# v7-flex2811_4x.net
KiCad netlist of a schematic drawn in EAGLE
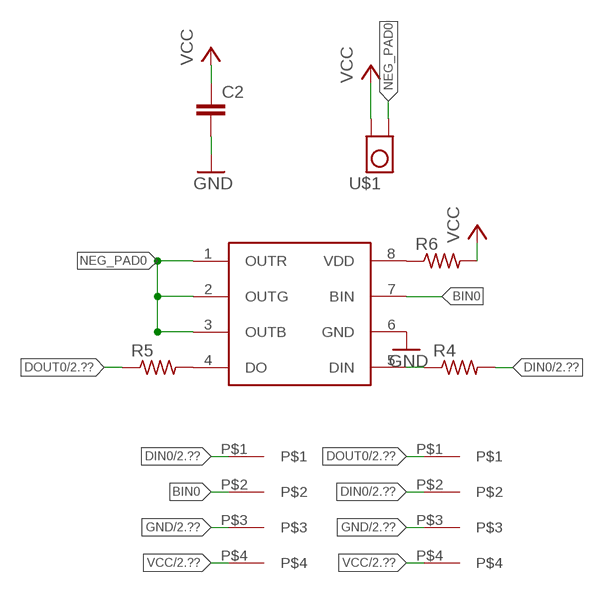
[diagram p0: schematic, sheet 1]
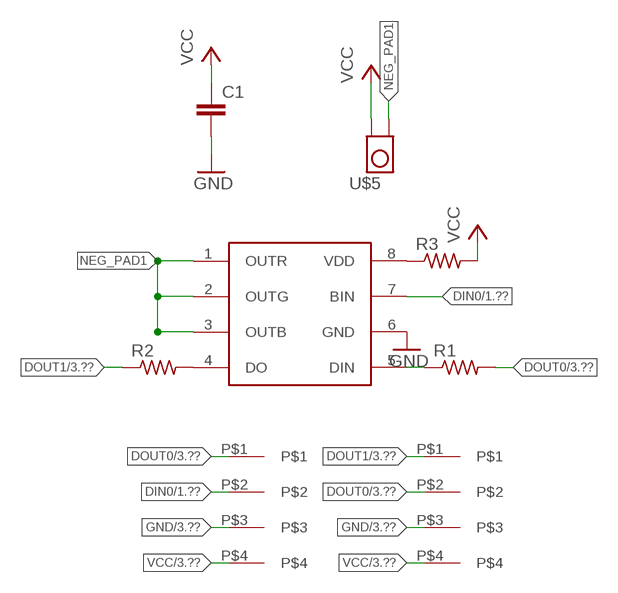
[diagram p1: schematic, sheet 2]
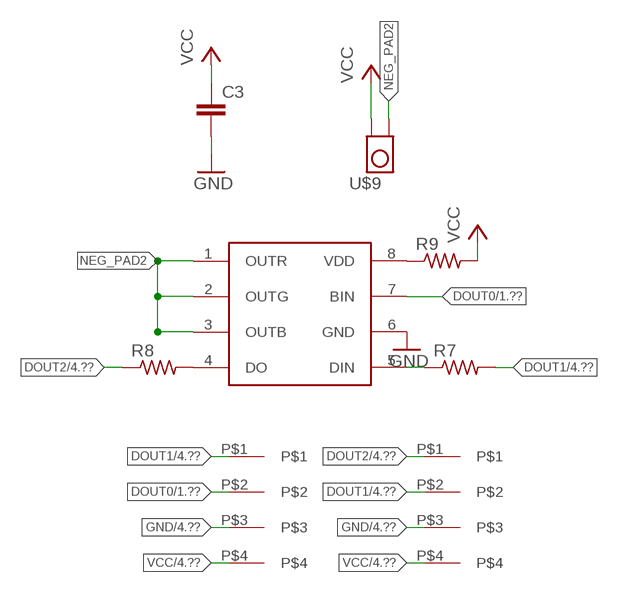
[diagram p2: schematic, sheet 3]
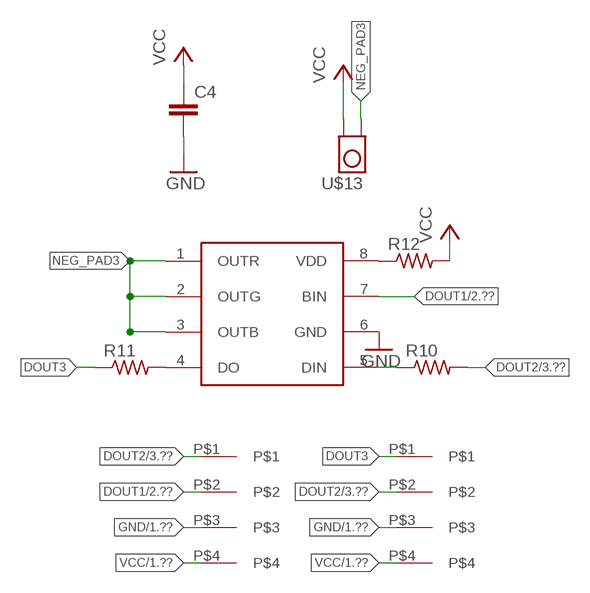
[diagram p3: schematic, sheet 4]

(export (version "E")
  (design (tool "Eeschema 10.0.6"))
  (components
    (comp (ref "C1")
      (value "C-EUC0201")
      (footprint "eagle-import:C0201")
      (libsource (lib "eagle-import") (part "C-EUC0201"))
    )
    (comp (ref "R1")
      (value "R-US_R0201")
      (footprint "eagle-import:R0201")
      (libsource (lib "eagle-import") (part "R-US_R0201"))
    )
    (comp (ref "R2")
      (value "R-US_R0201")
      (footprint "eagle-import:R0201")
      (libsource (lib "eagle-import") (part "R-US_R0201"))
    )
    (comp (ref "R3")
      (value "R-US_R0201")
      (footprint "eagle-import:R0201")
      (libsource (lib "eagle-import") (part "R-US_R0201"))
    )
    (comp (ref "U$5")
      (value "TP_4MM_MED_PAD")
      (footprint "eagle-import:TP_4MM_MED_PAD")
      (libsource (lib "eagle-import") (part "TP_4MM_MED_PAD"))
    )
    (comp (ref "U$6")
      (value "WS2818")
      (footprint "eagle-import:SO08")
      (libsource (lib "eagle-import") (part "WS2818"))
    )
    (comp (ref "U$7")
      (value "4PAD")
      (footprint "eagle-import:4PAD")
      (libsource (lib "eagle-import") (part "4PAD"))
    )
    (comp (ref "U$8")
      (value "4PAD")
      (footprint "eagle-import:4PAD")
      (libsource (lib "eagle-import") (part "4PAD"))
    )
    (comp (ref "C2")
      (value "C-EUC0201")
      (footprint "eagle-import:C0201")
      (libsource (lib "eagle-import") (part "C-EUC0201"))
    )
    (comp (ref "R4")
      (value "R-US_R0201")
      (footprint "eagle-import:R0201")
      (libsource (lib "eagle-import") (part "R-US_R0201"))
    )
    (comp (ref "R5")
      (value "R-US_R0201")
      (footprint "eagle-import:R0201")
      (libsource (lib "eagle-import") (part "R-US_R0201"))
    )
    (comp (ref "R6")
      (value "R-US_R0201")
      (footprint "eagle-import:R0201")
      (libsource (lib "eagle-import") (part "R-US_R0201"))
    )
    (comp (ref "U$1")
      (value "TP_4MM_MED_PAD")
      (footprint "eagle-import:TP_4MM_MED_PAD")
      (libsource (lib "eagle-import") (part "TP_4MM_MED_PAD"))
    )
    (comp (ref "U$2")
      (value "WS2818")
      (footprint "eagle-import:SO08")
      (libsource (lib "eagle-import") (part "WS2818"))
    )
    (comp (ref "U$3")
      (value "4PAD")
      (footprint "eagle-import:4PAD")
      (libsource (lib "eagle-import") (part "4PAD"))
    )
    (comp (ref "U$4")
      (value "4PAD")
      (footprint "eagle-import:4PAD")
      (libsource (lib "eagle-import") (part "4PAD"))
    )
    (comp (ref "C4")
      (value "C-EUC0201")
      (footprint "eagle-import:C0201")
      (libsource (lib "eagle-import") (part "C-EUC0201"))
    )
    (comp (ref "R10")
      (value "R-US_R0201")
      (footprint "eagle-import:R0201")
      (libsource (lib "eagle-import") (part "R-US_R0201"))
    )
    (comp (ref "R11")
      (value "R-US_R0201")
      (footprint "eagle-import:R0201")
      (libsource (lib "eagle-import") (part "R-US_R0201"))
    )
    (comp (ref "R12")
      (value "R-US_R0201")
      (footprint "eagle-import:R0201")
      (libsource (lib "eagle-import") (part "R-US_R0201"))
    )
    (comp (ref "U$13")
      (value "TP_4MM_MED_PAD")
      (footprint "eagle-import:TP_4MM_MED_PAD")
      (libsource (lib "eagle-import") (part "TP_4MM_MED_PAD"))
    )
    (comp (ref "U$14")
      (value "WS2818")
      (footprint "eagle-import:SO08")
      (libsource (lib "eagle-import") (part "WS2818"))
    )
    (comp (ref "U$15")
      (value "4PAD")
      (footprint "eagle-import:4PAD")
      (libsource (lib "eagle-import") (part "4PAD"))
    )
    (comp (ref "U$16")
      (value "4PAD")
      (footprint "eagle-import:4PAD")
      (libsource (lib "eagle-import") (part "4PAD"))
    )
    (comp (ref "C3")
      (value "C-EUC0201")
      (footprint "eagle-import:C0201")
      (libsource (lib "eagle-import") (part "C-EUC0201"))
    )
    (comp (ref "R7")
      (value "R-US_R0201")
      (footprint "eagle-import:R0201")
      (libsource (lib "eagle-import") (part "R-US_R0201"))
    )
    (comp (ref "R8")
      (value "R-US_R0201")
      (footprint "eagle-import:R0201")
      (libsource (lib "eagle-import") (part "R-US_R0201"))
    )
    (comp (ref "R9")
      (value "R-US_R0201")
      (footprint "eagle-import:R0201")
      (libsource (lib "eagle-import") (part "R-US_R0201"))
    )
    (comp (ref "U$9")
      (value "TP_4MM_MED_PAD")
      (footprint "eagle-import:TP_4MM_MED_PAD")
      (libsource (lib "eagle-import") (part "TP_4MM_MED_PAD"))
    )
    (comp (ref "U$10")
      (value "WS2818")
      (footprint "eagle-import:SO08")
      (libsource (lib "eagle-import") (part "WS2818"))
    )
    (comp (ref "U$11")
      (value "4PAD")
      (footprint "eagle-import:4PAD")
      (libsource (lib "eagle-import") (part "4PAD"))
    )
    (comp (ref "U$12")
      (value "4PAD")
      (footprint "eagle-import:4PAD")
      (libsource (lib "eagle-import") (part "4PAD"))
    )
  )
  (nets
    (net (code "1") (name "BIN0") (class "Default")
      (node (ref "U$2") (pin "7") (pinfunction "BIN_7") (pintype "bidirectional"))
      (node (ref "U$3") (pin "P$2") (pinfunction "P$2_P$2") (pintype "bidirectional"))
    )
    (net (code "2") (name "DIN0") (class "Default")
      (node (ref "R4") (pin "2") (pinfunction "2_2") (pintype "passive"))
      (node (ref "U$3") (pin "P$1") (pinfunction "P$1_P$1") (pintype "bidirectional"))
      (node (ref "U$4") (pin "P$2") (pinfunction "P$2_P$2") (pintype "bidirectional"))
      (node (ref "U$6") (pin "7") (pinfunction "BIN_7") (pintype "bidirectional"))
      (node (ref "U$7") (pin "P$2") (pinfunction "P$2_P$2") (pintype "bidirectional"))
    )
    (net (code "3") (name "DOUT0") (class "Default")
      (node (ref "R1") (pin "2") (pinfunction "2_2") (pintype "passive"))
      (node (ref "R5") (pin "1") (pinfunction "1_1") (pintype "passive"))
      (node (ref "U$10") (pin "7") (pinfunction "BIN_7") (pintype "bidirectional"))
      (node (ref "U$11") (pin "P$2") (pinfunction "P$2_P$2") (pintype "bidirectional"))
      (node (ref "U$4") (pin "P$1") (pinfunction "P$1_P$1") (pintype "bidirectional"))
      (node (ref "U$7") (pin "P$1") (pinfunction "P$1_P$1") (pintype "bidirectional"))
      (node (ref "U$8") (pin "P$2") (pinfunction "P$2_P$2") (pintype "bidirectional"))
    )
    (net (code "4") (name "DOUT1") (class "Default")
      (node (ref "R2") (pin "1") (pinfunction "1_1") (pintype "passive"))
      (node (ref "R7") (pin "2") (pinfunction "2_2") (pintype "passive"))
      (node (ref "U$11") (pin "P$1") (pinfunction "P$1_P$1") (pintype "bidirectional"))
      (node (ref "U$12") (pin "P$2") (pinfunction "P$2_P$2") (pintype "bidirectional"))
      (node (ref "U$14") (pin "7") (pinfunction "BIN_7") (pintype "bidirectional"))
      (node (ref "U$15") (pin "P$2") (pinfunction "P$2_P$2") (pintype "bidirectional"))
      (node (ref "U$8") (pin "P$1") (pinfunction "P$1_P$1") (pintype "bidirectional"))
    )
    (net (code "5") (name "DOUT2") (class "Default")
      (node (ref "R10") (pin "2") (pinfunction "2_2") (pintype "passive"))
      (node (ref "R8") (pin "1") (pinfunction "1_1") (pintype "passive"))
      (node (ref "U$12") (pin "P$1") (pinfunction "P$1_P$1") (pintype "bidirectional"))
      (node (ref "U$15") (pin "P$1") (pinfunction "P$1_P$1") (pintype "bidirectional"))
      (node (ref "U$16") (pin "P$2") (pinfunction "P$2_P$2") (pintype "bidirectional"))
    )
    (net (code "6") (name "DOUT3") (class "Default")
      (node (ref "R11") (pin "1") (pinfunction "1_1") (pintype "passive"))
      (node (ref "U$16") (pin "P$1") (pinfunction "P$1_P$1") (pintype "bidirectional"))
    )
    (net (code "7") (name "GND") (class "Default")
      (node (ref "C1") (pin "2") (pinfunction "2_2") (pintype "passive"))
      (node (ref "C2") (pin "2") (pinfunction "2_2") (pintype "passive"))
      (node (ref "C3") (pin "2") (pinfunction "2_2") (pintype "passive"))
      (node (ref "C4") (pin "2") (pinfunction "2_2") (pintype "passive"))
      (node (ref "U$10") (pin "6") (pinfunction "GND_6") (pintype "bidirectional"))
      (node (ref "U$11") (pin "P$3") (pinfunction "P$3_P$3") (pintype "bidirectional"))
      (node (ref "U$12") (pin "P$3") (pinfunction "P$3_P$3") (pintype "bidirectional"))
      (node (ref "U$14") (pin "6") (pinfunction "GND_6") (pintype "bidirectional"))
      (node (ref "U$15") (pin "P$3") (pinfunction "P$3_P$3") (pintype "bidirectional"))
      (node (ref "U$16") (pin "P$3") (pinfunction "P$3_P$3") (pintype "bidirectional"))
      (node (ref "U$2") (pin "6") (pinfunction "GND_6") (pintype "bidirectional"))
      (node (ref "U$3") (pin "P$3") (pinfunction "P$3_P$3") (pintype "bidirectional"))
      (node (ref "U$4") (pin "P$3") (pinfunction "P$3_P$3") (pintype "bidirectional"))
      (node (ref "U$6") (pin "6") (pinfunction "GND_6") (pintype "bidirectional"))
      (node (ref "U$7") (pin "P$3") (pinfunction "P$3_P$3") (pintype "bidirectional"))
      (node (ref "U$8") (pin "P$3") (pinfunction "P$3_P$3") (pintype "bidirectional"))
    )
    (net (code "8") (name "NEG_PAD0") (class "Default")
      (node (ref "U$1") (pin "P$1") (pinfunction "0_P$1") (pintype "bidirectional"))
      (node (ref "U$2") (pin "1") (pinfunction "OUTR_1") (pintype "bidirectional"))
      (node (ref "U$2") (pin "2") (pinfunction "OUTG_2") (pintype "bidirectional"))
      (node (ref "U$2") (pin "3") (pinfunction "OUTB_3") (pintype "bidirectional"))
    )
    (net (code "9") (name "NEG_PAD1") (class "Default")
      (node (ref "U$5") (pin "P$1") (pinfunction "0_P$1") (pintype "bidirectional"))
      (node (ref "U$6") (pin "1") (pinfunction "OUTR_1") (pintype "bidirectional"))
      (node (ref "U$6") (pin "2") (pinfunction "OUTG_2") (pintype "bidirectional"))
      (node (ref "U$6") (pin "3") (pinfunction "OUTB_3") (pintype "bidirectional"))
    )
    (net (code "10") (name "NEG_PAD2") (class "Default")
      (node (ref "U$10") (pin "1") (pinfunction "OUTR_1") (pintype "bidirectional"))
      (node (ref "U$10") (pin "2") (pinfunction "OUTG_2") (pintype "bidirectional"))
      (node (ref "U$10") (pin "3") (pinfunction "OUTB_3") (pintype "bidirectional"))
      (node (ref "U$9") (pin "P$1") (pinfunction "0_P$1") (pintype "bidirectional"))
    )
    (net (code "11") (name "NEG_PAD3") (class "Default")
      (node (ref "U$13") (pin "P$1") (pinfunction "0_P$1") (pintype "bidirectional"))
      (node (ref "U$14") (pin "1") (pinfunction "OUTR_1") (pintype "bidirectional"))
      (node (ref "U$14") (pin "2") (pinfunction "OUTG_2") (pintype "bidirectional"))
      (node (ref "U$14") (pin "3") (pinfunction "OUTB_3") (pintype "bidirectional"))
    )
    (net (code "12") (name "Net-(U$2-DIN)") (class "Default")
      (node (ref "R4") (pin "1") (pinfunction "1_1") (pintype "passive"))
      (node (ref "U$2") (pin "5") (pinfunction "DIN_5") (pintype "bidirectional"))
    )
    (net (code "13") (name "Net-(U$2-DO)") (class "Default")
      (node (ref "R5") (pin "2") (pinfunction "2_2") (pintype "passive"))
      (node (ref "U$2") (pin "4") (pinfunction "DO_4") (pintype "bidirectional"))
    )
    (net (code "14") (name "Net-(U$2-VDD)") (class "Default")
      (node (ref "R6") (pin "1") (pinfunction "1_1") (pintype "passive"))
      (node (ref "U$2") (pin "8") (pinfunction "VDD_8") (pintype "bidirectional"))
    )
    (net (code "15") (name "Net-(U$6-DIN)") (class "Default")
      (node (ref "R1") (pin "1") (pinfunction "1_1") (pintype "passive"))
      (node (ref "U$6") (pin "5") (pinfunction "DIN_5") (pintype "bidirectional"))
    )
    (net (code "16") (name "Net-(U$6-DO)") (class "Default")
      (node (ref "R2") (pin "2") (pinfunction "2_2") (pintype "passive"))
      (node (ref "U$6") (pin "4") (pinfunction "DO_4") (pintype "bidirectional"))
    )
    (net (code "17") (name "Net-(U$6-VDD)") (class "Default")
      (node (ref "R3") (pin "1") (pinfunction "1_1") (pintype "passive"))
      (node (ref "U$6") (pin "8") (pinfunction "VDD_8") (pintype "bidirectional"))
    )
    (net (code "18") (name "Net-(U$10-DIN)") (class "Default")
      (node (ref "R7") (pin "1") (pinfunction "1_1") (pintype "passive"))
      (node (ref "U$10") (pin "5") (pinfunction "DIN_5") (pintype "bidirectional"))
    )
    (net (code "19") (name "Net-(U$10-DO)") (class "Default")
      (node (ref "R8") (pin "2") (pinfunction "2_2") (pintype "passive"))
      (node (ref "U$10") (pin "4") (pinfunction "DO_4") (pintype "bidirectional"))
    )
    (net (code "20") (name "Net-(U$10-VDD)") (class "Default")
      (node (ref "R9") (pin "1") (pinfunction "1_1") (pintype "passive"))
      (node (ref "U$10") (pin "8") (pinfunction "VDD_8") (pintype "bidirectional"))
    )
    (net (code "21") (name "Net-(U$14-DIN)") (class "Default")
      (node (ref "R10") (pin "1") (pinfunction "1_1") (pintype "passive"))
      (node (ref "U$14") (pin "5") (pinfunction "DIN_5") (pintype "bidirectional"))
    )
    (net (code "22") (name "Net-(U$14-DO)") (class "Default")
      (node (ref "R11") (pin "2") (pinfunction "2_2") (pintype "passive"))
      (node (ref "U$14") (pin "4") (pinfunction "DO_4") (pintype "bidirectional"))
    )
    (net (code "23") (name "Net-(U$14-VDD)") (class "Default")
      (node (ref "R12") (pin "1") (pinfunction "1_1") (pintype "passive"))
      (node (ref "U$14") (pin "8") (pinfunction "VDD_8") (pintype "bidirectional"))
    )
    (net (code "24") (name "VCC") (class "Default")
      (node (ref "C1") (pin "1") (pinfunction "1_1") (pintype "passive"))
      (node (ref "C2") (pin "1") (pinfunction "1_1") (pintype "passive"))
      (node (ref "C3") (pin "1") (pinfunction "1_1") (pintype "passive"))
      (node (ref "C4") (pin "1") (pinfunction "1_1") (pintype "passive"))
      (node (ref "R12") (pin "2") (pinfunction "2_2") (pintype "passive"))
      (node (ref "R3") (pin "2") (pinfunction "2_2") (pintype "passive"))
      (node (ref "R6") (pin "2") (pinfunction "2_2") (pintype "passive"))
      (node (ref "R9") (pin "2") (pinfunction "2_2") (pintype "passive"))
      (node (ref "U$1") (pin "P$2") (pinfunction "1_P$2") (pintype "bidirectional"))
      (node (ref "U$11") (pin "P$4") (pinfunction "P$4_P$4") (pintype "bidirectional"))
      (node (ref "U$12") (pin "P$4") (pinfunction "P$4_P$4") (pintype "bidirectional"))
      (node (ref "U$13") (pin "P$2") (pinfunction "1_P$2") (pintype "bidirectional"))
      (node (ref "U$15") (pin "P$4") (pinfunction "P$4_P$4") (pintype "bidirectional"))
      (node (ref "U$16") (pin "P$4") (pinfunction "P$4_P$4") (pintype "bidirectional"))
      (node (ref "U$3") (pin "P$4") (pinfunction "P$4_P$4") (pintype "bidirectional"))
      (node (ref "U$4") (pin "P$4") (pinfunction "P$4_P$4") (pintype "bidirectional"))
      (node (ref "U$5") (pin "P$2") (pinfunction "1_P$2") (pintype "bidirectional"))
      (node (ref "U$7") (pin "P$4") (pinfunction "P$4_P$4") (pintype "bidirectional"))
      (node (ref "U$8") (pin "P$4") (pinfunction "P$4_P$4") (pintype "bidirectional"))
      (node (ref "U$9") (pin "P$2") (pinfunction "1_P$2") (pintype "bidirectional"))
    )
  )
)
